# 400_TEENSY.net
KiCad netlist of a schematic drawn in Altium Designer
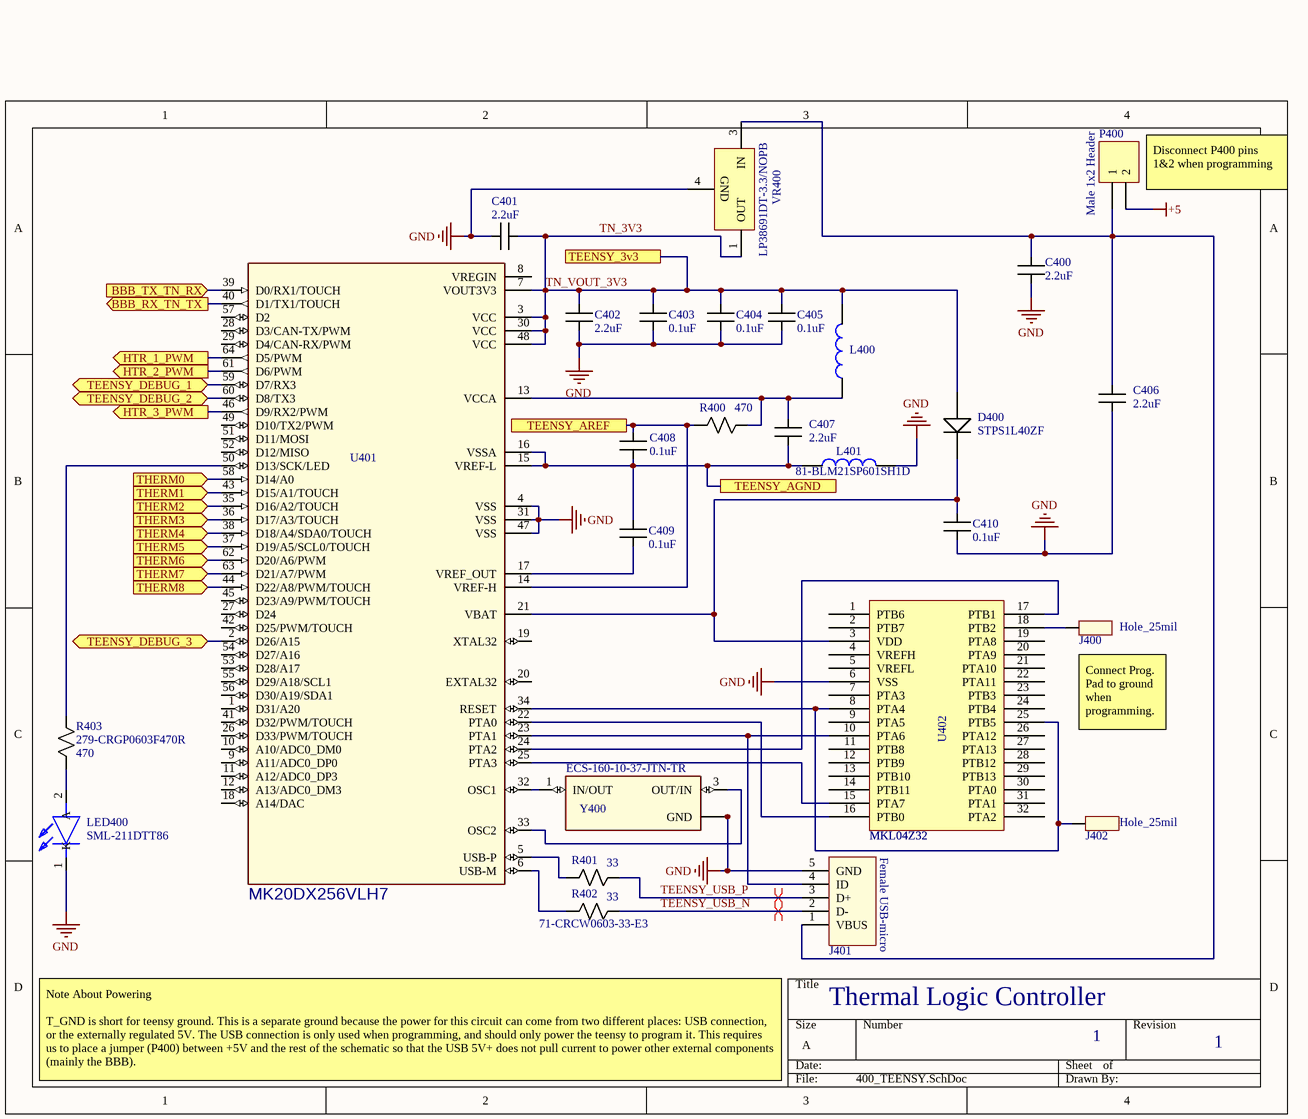
[diagram p0: 400_TEENSY.SchDoc]

(export (version "E")
  (design (tool "Eeschema 10.0.6"))
  (components
    (comp (ref "C400")
      (value "2.2uF")
      (footprint "IMPERIAL0603_Capacitor")
      (description "2.2uF Capacitor, Non Polarized Chip Cap")
      (fields (field (name "Comment") "2.2uF Capacitor"))
      (libsource (lib "OASIS_COMPONENTS_SYMBOLS") (part "LMK107BJ225KK-T"))
    )
    (comp (ref "C401")
      (value "2.2uF")
      (footprint "IMPERIAL0603_Capacitor")
      (description "2.2uF Capacitor, Non Polarized Chip Cap")
      (fields (field (name "Comment") "2.2uF Capacitor"))
      (libsource (lib "OASIS_COMPONENTS_SYMBOLS") (part "LMK107BJ225KK-T"))
    )
    (comp (ref "C402")
      (value "2.2uF")
      (footprint "IMPERIAL0603_Capacitor")
      (description "2.2uF Capacitor, Non Polarized Chip Cap")
      (fields (field (name "Comment") "2.2uF Capacitor"))
      (libsource (lib "OASIS_COMPONENTS_SYMBOLS") (part "LMK107BJ225KK-T"))
    )
    (comp (ref "C403")
      (value "0.1uF")
      (footprint "IMPERIAL0603_Capacitor")
      (description "0.1uF capacitor, Non Polarized Chip Cap")
      (fields (field (name "Comment") "0.1uF Capactor"))
      (libsource (lib "OASIS_COMPONENTS_SYMBOLS") (part "TMK107BJ104KA-T"))
    )
    (comp (ref "C404")
      (value "0.1uF")
      (footprint "IMPERIAL0603_Capacitor")
      (description "0.1uF capacitor, Non Polarized Chip Cap")
      (fields (field (name "Comment") "0.1uF Capactor"))
      (libsource (lib "OASIS_COMPONENTS_SYMBOLS") (part "TMK107BJ104KA-T"))
    )
    (comp (ref "C405")
      (value "0.1uF")
      (footprint "IMPERIAL0603_Capacitor")
      (description "0.1uF capacitor, Non Polarized Chip Cap")
      (fields (field (name "Comment") "0.1uF Capactor"))
      (libsource (lib "OASIS_COMPONENTS_SYMBOLS") (part "TMK107BJ104KA-T"))
    )
    (comp (ref "C406")
      (value "2.2uF")
      (footprint "IMPERIAL0603_Capacitor")
      (description "2.2uF Capacitor, Non Polarized Chip Cap")
      (fields (field (name "Comment") "2.2uF Capacitor"))
      (libsource (lib "OASIS_COMPONENTS_SYMBOLS") (part "LMK107BJ225KK-T"))
    )
    (comp (ref "C407")
      (value "2.2uF")
      (footprint "IMPERIAL0603_Capacitor")
      (description "2.2uF Capacitor, Non Polarized Chip Cap")
      (fields (field (name "Comment") "2.2uF Capacitor"))
      (libsource (lib "OASIS_COMPONENTS_SYMBOLS") (part "LMK107BJ225KK-T"))
    )
    (comp (ref "C408")
      (value "0.1uF")
      (footprint "IMPERIAL0603_Capacitor")
      (description "0.1uF capacitor, Non Polarized Chip Cap")
      (fields (field (name "Comment") "0.1uF Capactor"))
      (libsource (lib "OASIS_COMPONENTS_SYMBOLS") (part "TMK107BJ104KA-T"))
    )
    (comp (ref "C409")
      (value "0.1uF")
      (footprint "IMPERIAL0603_Capacitor")
      (description "0.1uF capacitor, Non Polarized Chip Cap")
      (fields (field (name "Comment") "0.1uF Capactor"))
      (libsource (lib "OASIS_COMPONENTS_SYMBOLS") (part "TMK107BJ104KA-T"))
    )
    (comp (ref "C410")
      (value "0.1uF")
      (footprint "IMPERIAL0603_Capacitor")
      (description "0.1uF capacitor, Non Polarized Chip Cap")
      (fields (field (name "Comment") "0.1uF Capactor"))
      (libsource (lib "OASIS_COMPONENTS_SYMBOLS") (part "TMK107BJ104KA-T"))
    )
    (comp (ref "D400")
      (value "STPS1L40ZF")
      (footprint "*SODFL3718X108N")
      (description "1A Schottky Diode")
      (libsource (lib "OASIS_COMPONENTS_SYMBOLS") (part "STPS1L40ZF"))
    )
    (comp (ref "J400")
      (value "Hole_25mil")
      (footprint "PAD_40x25")
      (description "40 mil solder pad - 25 mil hole")
      (libsource (lib "OASIS_COMPONENTS_SYMBOLS") (part "Hole_25mil"))
    )
    (comp (ref "J401")
      (value "uUSB Padsonly")
      (footprint "uUSB_Padsonly")
      (description "Micro USB Connection - solder pads only")
      (libsource (lib "OASIS_COMPONENTS_SYMBOLS") (part "uUSB_Padsonly"))
    )
    (comp (ref "J402")
      (value "Hole_25mil")
      (footprint "PAD_40x25")
      (description "40 mil solder pad - 25 mil hole")
      (libsource (lib "OASIS_COMPONENTS_SYMBOLS") (part "Hole_25mil"))
    )
    (comp (ref "L400")
      (value "Ferritde, 600 Ohm Impedence")
      (footprint "Imperial0805_RES")
      (description "Ferrite Bead, 600 Ohm Impedence for TLC")
      (fields (field (name "SUPPLIER PART NUMBER 1") "81-BLM21SP601SH1D"))
      (libsource (lib "OASIS_COMPONENTS_SYMBOLS") (part "BLM21SP601SH1D"))
    )
    (comp (ref "L401")
      (value "Ferritde, 600 Ohm Impedence")
      (footprint "Imperial0805_RES")
      (description "Ferrite Bead, 600 Ohm Impedence for TLC")
      (libsource (lib "OASIS_COMPONENTS_SYMBOLS") (part "BLM21SP601SH1D"))
    )
    (comp (ref "LED400")
      (value "SML-211DTT86")
      (footprint "OASIS_COMPONENTS_FOOTPRINTS:LEDC2012X90N")
      (description "LED")
      (libsource (lib "OASIS_COMPONENTS_SYMBOLS") (part "SML-211DTT86"))
    )
    (comp (ref "P400")
      (value "Header 2")
      (footprint "HDR1X2")
      (description "Header, 2-Pin")
      (fields (field (name "PUBLISHER") "Altium Limited"))
      (libsource (lib "Miscellaneous Connectors") (part "Header 2"))
    )
    (comp (ref "R400")
      (value "470")
      (footprint "Imperial0603_RES")
      (description "470 Ohm Generic Chip Resistor")
      (fields (field (name "Comment") "470 Ohm Resistor"))
      (libsource (lib "OASIS_COMPONENTS_SYMBOLS") (part "CRGP0603F470R"))
    )
    (comp (ref "R401")
      (value "33")
      (footprint "Imperial0603_RES")
      (description "33 Ohm Generic Chip Resistor")
      (fields (field (name "Comment") "33 Ohm Resistor"))
      (libsource (lib "OASIS_COMPONENTS_SYMBOLS") (part "CRCW060333R0FKEAC"))
    )
    (comp (ref "R402")
      (value "33")
      (footprint "Imperial0603_RES")
      (description "33 Ohm Generic Chip Resistor")
      (fields
        (field (name "SUPPLIER PART NUMBER 1") "71-CRCW0603-33-E3")
        (field (name "Comment") "33 Ohm Resistor")
      )
      (libsource (lib "OASIS_COMPONENTS_SYMBOLS") (part "CRCW060333R0FKEAC"))
    )
    (comp (ref "R403")
      (value "470")
      (footprint "Imperial0603_RES")
      (description "470 Ohm Generic Chip Resistor")
      (fields
        (field (name "SUPPLIER PART NUMBER 1") "279-CRGP0603F470R")
        (field (name "Comment") "470 Ohm Resistor")
      )
      (libsource (lib "OASIS_COMPONENTS_SYMBOLS") (part "CRGP0603F470R"))
    )
    (comp (ref "U401")
      (value "MK20DX256VLH7")
      (footprint "*QFP50P1200X1200X160-64N")
      (description "MCU 32-bit Kinetis K20 ARM Cortex M4 RISC 256KB Flash 1.8V/2.5V/3.3V 64-Pin LQFP Tray")
      (fields (field (name "MF") "NXP USA") (field (name "MP") "MK20DX256VLH7"))
      (libsource (lib "OASIS_COMPONENTS_SYMBOLS") (part "MK20DX256VLH7"))
    )
    (comp (ref "U402")
      (value "MKL04Z32")
      (footprint "*QFP80P900X900X160-32N")
      (description "Bootloader chip for teensy 3.2")
      (fields (field (name "PART NUMBER") "MKL04Z32"))
      (libsource (lib "OASIS_COMPONENTS_SYMBOLS") (part "MKL04Z32"))
    )
    (comp (ref "VR400")
      (value "LP38691DT-3.3/NOPB")
      (footprint "NDP0003B_N")
      (fields (field (name "MANUFACTURER") "Texas Instruments"))
      (libsource (lib "OASIS_COMPONENTS_SYMBOLS") (part "CMP-0062-00443-4"))
    )
    (comp (ref "Y400")
      (value "ECS-160-10-37-JTN-TR")
      (footprint "XTAL_ECS-160-10-37-RWM-TR")
      (description "Crystal 16MHz")
      (fields (field (name "DIGI-KEY_PART_NUMBER") "XC2119CT-ND") (field (name "MF") "ECS Inc."))
      (libsource (lib "OASIS_COMPONENTS_SYMBOLS") (part "ECS-160-10-37-JTN-TR"))
    )
  )
  (nets
    (net (code "1") (name "+5") (class "Default")
      (node (ref "P400") (pin "2") (pinfunction "2_2") (pintype "passive"))
    )
    (net (code "2") (name "/BBB_RX_TN_TX") (class "Default")
      (node (ref "U401") (pin "40") (pinfunction "D1/TX1/TOUCH_40") (pintype "output"))
    )
    (net (code "3") (name "/BBB_TX_TN_RX") (class "Default")
      (node (ref "U401") (pin "39") (pinfunction "D0/RX1/TOUCH_39") (pintype "input"))
    )
    (net (code "4") (name "/HTR_1_PWM") (class "Default")
      (node (ref "U401") (pin "64") (pinfunction "D5/PWM_64") (pintype "output"))
    )
    (net (code "5") (name "/HTR_2_PWM") (class "Default")
      (node (ref "U401") (pin "61") (pinfunction "D6/PWM_61") (pintype "output"))
    )
    (net (code "6") (name "/HTR_3_PWM") (class "Default")
      (node (ref "U401") (pin "46") (pinfunction "D9/RX2/PWM_46") (pintype "output"))
    )
    (net (code "7") (name "/TEENSY_AGND") (class "Default")
      (node (ref "C407") (pin "2") (pinfunction "2_2") (pintype "passive"))
      (node (ref "C408") (pin "2") (pinfunction "2_2") (pintype "passive"))
      (node (ref "C409") (pin "1") (pinfunction "1_1") (pintype "passive"))
      (node (ref "L401") (pin "1") (pinfunction "1_1") (pintype "passive"))
      (node (ref "U401") (pin "15") (pinfunction "VREF-L_15") (pintype "power_in"))
      (node (ref "U401") (pin "16") (pinfunction "VSSA_16") (pintype "power_in"))
    )
    (net (code "8") (name "/TEENSY_AREF") (class "Default")
      (node (ref "C408") (pin "1") (pinfunction "1_1") (pintype "passive"))
      (node (ref "R400") (pin "1") (pinfunction "1_1") (pintype "passive"))
      (node (ref "U401") (pin "14") (pinfunction "VREF-H_14") (pintype "power_in"))
    )
    (net (code "9") (name "/TEENSY_DEBUG_1") (class "Default")
      (node (ref "U401") (pin "59") (pinfunction "D7/RX3_59") (pintype "bidirectional"))
    )
    (net (code "10") (name "/TEENSY_DEBUG_2") (class "Default")
      (node (ref "U401") (pin "60") (pinfunction "D8/TX3_60") (pintype "bidirectional"))
    )
    (net (code "11") (name "/TEENSY_DEBUG_3") (class "Default")
      (node (ref "U401") (pin "2") (pinfunction "D26/A15_2") (pintype "bidirectional"))
    )
    (net (code "12") (name "/TEENSY_USB_N") (class "Default")
      (node (ref "J401") (pin "2") (pinfunction "D-_2") (pintype "passive"))
      (node (ref "R402") (pin "2") (pinfunction "2_2") (pintype "passive"))
    )
    (net (code "13") (name "/TEENSY_USB_P") (class "Default")
      (node (ref "J401") (pin "3") (pinfunction "D+_3") (pintype "passive"))
      (node (ref "R401") (pin "2") (pinfunction "2_2") (pintype "passive"))
    )
    (net (code "14") (name "/THERM0") (class "Default")
      (node (ref "U401") (pin "58") (pinfunction "D14/A0_58") (pintype "input"))
    )
    (net (code "15") (name "/THERM1") (class "Default")
      (node (ref "U401") (pin "43") (pinfunction "D15/A1/TOUCH_43") (pintype "input"))
    )
    (net (code "16") (name "/THERM2") (class "Default")
      (node (ref "U401") (pin "35") (pinfunction "D16/A2/TOUCH_35") (pintype "input"))
    )
    (net (code "17") (name "/THERM3") (class "Default")
      (node (ref "U401") (pin "36") (pinfunction "D17/A3/TOUCH_36") (pintype "input"))
    )
    (net (code "18") (name "/THERM4") (class "Default")
      (node (ref "U401") (pin "38") (pinfunction "D18/A4/SDA0/TOUCH_38") (pintype "input"))
    )
    (net (code "19") (name "/THERM5") (class "Default")
      (node (ref "U401") (pin "37") (pinfunction "D19/A5/SCL0/TOUCH_37") (pintype "input"))
    )
    (net (code "20") (name "/THERM6") (class "Default")
      (node (ref "U401") (pin "62") (pinfunction "D20/A6/PWM_62") (pintype "input"))
    )
    (net (code "21") (name "/THERM7") (class "Default")
      (node (ref "U401") (pin "63") (pinfunction "D21/A7/PWM_63") (pintype "input"))
    )
    (net (code "22") (name "/THERM8") (class "Default")
      (node (ref "U401") (pin "44") (pinfunction "D22/A8/PWM/TOUCH_44") (pintype "input"))
    )
    (net (code "23") (name "/TN_3V3") (class "Default")
      (node (ref "C401") (pin "1") (pinfunction "1_1") (pintype "passive"))
      (node (ref "C402") (pin "1") (pinfunction "1_1") (pintype "passive"))
      (node (ref "C403") (pin "1") (pinfunction "1_1") (pintype "passive"))
      (node (ref "C404") (pin "1") (pinfunction "1_1") (pintype "passive"))
      (node (ref "C405") (pin "1") (pinfunction "1_1") (pintype "passive"))
      (node (ref "D400") (pin "2") (pinfunction "anode_2") (pintype "passive"))
      (node (ref "L400") (pin "2") (pinfunction "2_2") (pintype "passive"))
      (node (ref "U401") (pin "3") (pinfunction "VCC_3") (pintype "power_in"))
      (node (ref "U401") (pin "30") (pinfunction "VCC_30") (pintype "power_in"))
      (node (ref "U401") (pin "48") (pinfunction "VCC_48") (pintype "power_in"))
      (node (ref "U401") (pin "7") (pinfunction "VOUT3V3_7") (pintype "power_in"))
      (node (ref "VR400") (pin "1") (pinfunction "OUT_1") (pintype "power_in"))
    )
    (net (code "24") (name "GND") (class "Default")
      (node (ref "C400") (pin "2") (pinfunction "2_2") (pintype "passive"))
      (node (ref "C401") (pin "2") (pinfunction "2_2") (pintype "passive"))
      (node (ref "C402") (pin "2") (pinfunction "2_2") (pintype "passive"))
      (node (ref "C403") (pin "2") (pinfunction "2_2") (pintype "passive"))
      (node (ref "C404") (pin "2") (pinfunction "2_2") (pintype "passive"))
      (node (ref "C405") (pin "2") (pinfunction "2_2") (pintype "passive"))
      (node (ref "C406") (pin "2") (pinfunction "2_2") (pintype "passive"))
      (node (ref "C410") (pin "2") (pinfunction "2_2") (pintype "passive"))
      (node (ref "J401") (pin "5") (pinfunction "GND_5") (pintype "passive"))
      (node (ref "L401") (pin "2") (pinfunction "2_2") (pintype "passive"))
      (node (ref "LED400") (pin "1") (pinfunction "K_1") (pintype "passive"))
      (node (ref "U401") (pin "31") (pinfunction "VSS_31") (pintype "power_in"))
      (node (ref "U401") (pin "4") (pinfunction "VSS_4") (pintype "power_in"))
      (node (ref "U401") (pin "47") (pinfunction "VSS_47") (pintype "power_in"))
      (node (ref "U402") (pin "6") (pinfunction "VSS_6") (pintype "passive"))
      (node (ref "VR400") (pin "4") (pinfunction "GND_4") (pintype "power_in"))
      (node (ref "Y400") (pin "2") (pinfunction "GND_2") (pintype "power_in"))
      (node (ref "Y400") (pin "4") (pinfunction "GND_4") (pintype "power_in"))
    )
    (net (code "25") (name "Net-(D400-cathode)") (class "Default")
      (node (ref "C410") (pin "1") (pinfunction "1_1") (pintype "passive"))
      (node (ref "D400") (pin "1") (pinfunction "cathode_1") (pintype "passive"))
      (node (ref "U401") (pin "21") (pinfunction "VBAT_21") (pintype "power_in"))
      (node (ref "U402") (pin "3") (pinfunction "VDD_3") (pintype "passive"))
    )
    (net (code "26") (name "Net-(J400-PIN)") (class "Default")
      (node (ref "J400") (pin "1") (pinfunction "PIN_1") (pintype "passive"))
      (node (ref "U402") (pin "18") (pinfunction "PTB2_18") (pintype "passive"))
    )
    (net (code "27") (name "Net-(J401-ID)") (class "Default")
      (node (ref "J401") (pin "4") (pinfunction "ID_4") (pintype "passive"))
      (node (ref "U401") (pin "23") (pinfunction "PTA1_23") (pintype "bidirectional"))
      (node (ref "U402") (pin "10") (pinfunction "PTA6_10") (pintype "passive"))
    )
    (net (code "28") (name "Net-(J401-VBUS)") (class "Default")
      (node (ref "C400") (pin "1") (pinfunction "1_1") (pintype "passive"))
      (node (ref "C406") (pin "1") (pinfunction "1_1") (pintype "passive"))
      (node (ref "J401") (pin "1") (pinfunction "VBUS_1") (pintype "passive"))
      (node (ref "P400") (pin "1") (pinfunction "1_1") (pintype "passive"))
      (node (ref "VR400") (pin "3") (pinfunction "IN_3") (pintype "power_in"))
    )
    (net (code "29") (name "Net-(J402-PIN)") (class "Default")
      (node (ref "J402") (pin "1") (pinfunction "PIN_1") (pintype "passive"))
      (node (ref "U401") (pin "34") (pinfunction "RESET_34") (pintype "bidirectional"))
      (node (ref "U402") (pin "25") (pinfunction "PTB5_25") (pintype "passive"))
      (node (ref "U402") (pin "8") (pinfunction "PTA4_8") (pintype "passive"))
    )
    (net (code "30") (name "Net-(LED400-A)") (class "Default")
      (node (ref "LED400") (pin "2") (pinfunction "A_2") (pintype "passive"))
      (node (ref "R403") (pin "1") (pinfunction "1_1") (pintype "passive"))
    )
    (net (code "31") (name "Net-(U401-D13{slash}SCK{slash}LED)") (class "Default")
      (node (ref "R403") (pin "2") (pinfunction "2_2") (pintype "passive"))
      (node (ref "U401") (pin "50") (pinfunction "D13/SCK/LED_50") (pintype "bidirectional"))
    )
    (net (code "32") (name "Net-(U401-OSC1)") (class "Default")
      (node (ref "U401") (pin "32") (pinfunction "OSC1_32") (pintype "bidirectional"))
      (node (ref "Y400") (pin "1") (pinfunction "IN/OUT_1") (pintype "bidirectional"))
    )
    (net (code "33") (name "Net-(U401-OSC2)") (class "Default")
      (node (ref "U401") (pin "33") (pinfunction "OSC2_33") (pintype "bidirectional"))
      (node (ref "Y400") (pin "3") (pinfunction "OUT/IN_3") (pintype "bidirectional"))
    )
    (net (code "34") (name "Net-(U401-PTA0)") (class "Default")
      (node (ref "U401") (pin "22") (pinfunction "PTA0_22") (pintype "bidirectional"))
      (node (ref "U402") (pin "16") (pinfunction "PTB0_16") (pintype "passive"))
    )
    (net (code "35") (name "Net-(U401-PTA2)") (class "Default")
      (node (ref "U401") (pin "24") (pinfunction "PTA2_24") (pintype "bidirectional"))
      (node (ref "U402") (pin "17") (pinfunction "PTB1_17") (pintype "passive"))
    )
    (net (code "36") (name "Net-(U401-PTA3)") (class "Default")
      (node (ref "U401") (pin "25") (pinfunction "PTA3_25") (pintype "bidirectional"))
      (node (ref "U402") (pin "15") (pinfunction "PTA7_15") (pintype "passive"))
    )
    (net (code "37") (name "Net-(U401-USB-M)") (class "Default")
      (node (ref "R402") (pin "1") (pinfunction "1_1") (pintype "passive"))
      (node (ref "U401") (pin "6") (pinfunction "USB-M_6") (pintype "bidirectional"))
    )
    (net (code "38") (name "Net-(U401-USB-P)") (class "Default")
      (node (ref "R401") (pin "1") (pinfunction "1_1") (pintype "passive"))
      (node (ref "U401") (pin "5") (pinfunction "USB-P_5") (pintype "bidirectional"))
    )
    (net (code "39") (name "Net-(U401-VCCA)") (class "Default")
      (node (ref "C407") (pin "1") (pinfunction "1_1") (pintype "passive"))
      (node (ref "L400") (pin "1") (pinfunction "1_1") (pintype "passive"))
      (node (ref "R400") (pin "2") (pinfunction "2_2") (pintype "passive"))
      (node (ref "U401") (pin "13") (pinfunction "VCCA_13") (pintype "power_in"))
    )
    (net (code "40") (name "Net-(U401-VREF_OUT)") (class "Default")
      (node (ref "C409") (pin "2") (pinfunction "2_2") (pintype "passive"))
      (node (ref "U401") (pin "17") (pinfunction "VREF_OUT_17") (pintype "power_in"))
    )
    (net (code "41") (name "unconnected-(U401-A10{slash}ADC0_DM0-Pad10)") (class "Default")
      (node (ref "U401") (pin "10") (pinfunction "A10/ADC0_DM0_10") (pintype "bidirectional"))
    )
    (net (code "42") (name "unconnected-(U401-A11{slash}ADC0_DP0-Pad9)") (class "Default")
      (node (ref "U401") (pin "9") (pinfunction "A11/ADC0_DP0_9") (pintype "bidirectional"))
    )
    (net (code "43") (name "unconnected-(U401-A12{slash}ADC0_DP3-Pad11)") (class "Default")
      (node (ref "U401") (pin "11") (pinfunction "A12/ADC0_DP3_11") (pintype "bidirectional"))
    )
    (net (code "44") (name "unconnected-(U401-A13{slash}ADC0_DM3-Pad12)") (class "Default")
      (node (ref "U401") (pin "12") (pinfunction "A13/ADC0_DM3_12") (pintype "bidirectional"))
    )
    (net (code "45") (name "unconnected-(U401-A14{slash}DAC-Pad18)") (class "Default")
      (node (ref "U401") (pin "18") (pinfunction "A14/DAC_18") (pintype "bidirectional"))
    )
    (net (code "46") (name "unconnected-(U401-D2-Pad57)") (class "Default")
      (node (ref "U401") (pin "57") (pinfunction "D2_57") (pintype "bidirectional"))
    )
    (net (code "47") (name "unconnected-(U401-D3{slash}CAN-TX{slash}PWM-Pad28)") (class "Default")
      (node (ref "U401") (pin "28") (pinfunction "D3/CAN-TX/PWM_28") (pintype "bidirectional"))
    )
    (net (code "48") (name "unconnected-(U401-D4{slash}CAN-RX{slash}PWM-Pad29)") (class "Default")
      (node (ref "U401") (pin "29") (pinfunction "D4/CAN-RX/PWM_29") (pintype "bidirectional"))
    )
    (net (code "49") (name "unconnected-(U401-D10{slash}TX2{slash}PWM-Pad49)") (class "Default")
      (node (ref "U401") (pin "49") (pinfunction "D10/TX2/PWM_49") (pintype "bidirectional"))
    )
    (net (code "50") (name "unconnected-(U401-D11{slash}MOSI-Pad51)") (class "Default")
      (node (ref "U401") (pin "51") (pinfunction "D11/MOSI_51") (pintype "bidirectional"))
    )
    (net (code "51") (name "unconnected-(U401-D12{slash}MISO-Pad52)") (class "Default")
      (node (ref "U401") (pin "52") (pinfunction "D12/MISO_52") (pintype "bidirectional"))
    )
    (net (code "52") (name "unconnected-(U401-D23{slash}A9{slash}PWM{slash}TOUCH-Pad45)") (class "Default")
      (node (ref "U401") (pin "45") (pinfunction "D23/A9/PWM/TOUCH_45") (pintype "bidirectional"))
    )
    (net (code "53") (name "unconnected-(U401-D24-Pad27)") (class "Default")
      (node (ref "U401") (pin "27") (pinfunction "D24_27") (pintype "bidirectional"))
    )
    (net (code "54") (name "unconnected-(U401-D25{slash}PWM{slash}TOUCH-Pad42)") (class "Default")
      (node (ref "U401") (pin "42") (pinfunction "D25/PWM/TOUCH_42") (pintype "bidirectional"))
    )
    (net (code "55") (name "unconnected-(U401-D27{slash}A16-Pad54)") (class "Default")
      (node (ref "U401") (pin "54") (pinfunction "D27/A16_54") (pintype "bidirectional"))
    )
    (net (code "56") (name "unconnected-(U401-D28{slash}A17-Pad53)") (class "Default")
      (node (ref "U401") (pin "53") (pinfunction "D28/A17_53") (pintype "bidirectional"))
    )
    (net (code "57") (name "unconnected-(U401-D29{slash}A18{slash}SCL1-Pad55)") (class "Default")
      (node (ref "U401") (pin "55") (pinfunction "D29/A18/SCL1_55") (pintype "bidirectional"))
    )
    (net (code "58") (name "unconnected-(U401-D30{slash}A19{slash}SDA1-Pad56)") (class "Default")
      (node (ref "U401") (pin "56") (pinfunction "D30/A19/SDA1_56") (pintype "bidirectional"))
    )
    (net (code "59") (name "unconnected-(U401-D31{slash}A20-Pad1)") (class "Default")
      (node (ref "U401") (pin "1") (pinfunction "D31/A20_1") (pintype "bidirectional"))
    )
    (net (code "60") (name "unconnected-(U401-D32{slash}PWM{slash}TOUCH-Pad41)") (class "Default")
      (node (ref "U401") (pin "41") (pinfunction "D32/PWM/TOUCH_41") (pintype "bidirectional"))
    )
    (net (code "61") (name "unconnected-(U401-D33{slash}PWM{slash}TOUCH-Pad26)") (class "Default")
      (node (ref "U401") (pin "26") (pinfunction "D33/PWM/TOUCH_26") (pintype "bidirectional"))
    )
    (net (code "62") (name "unconnected-(U401-EXTAL32-Pad20)") (class "Default")
      (node (ref "U401") (pin "20") (pinfunction "EXTAL32_20") (pintype "bidirectional"))
    )
    (net (code "63") (name "unconnected-(U401-VREGIN-Pad8)") (class "Default")
      (node (ref "U401") (pin "8") (pinfunction "VREGIN_8") (pintype "power_in"))
    )
    (net (code "64") (name "unconnected-(U401-XTAL32-Pad19)") (class "Default")
      (node (ref "U401") (pin "19") (pinfunction "XTAL32_19") (pintype "bidirectional"))
    )
    (net (code "65") (name "unconnected-(U402-PTA0-Pad30)") (class "Default")
      (node (ref "U402") (pin "30") (pinfunction "PTA0_30") (pintype "passive"))
    )
    (net (code "66") (name "unconnected-(U402-PTA1-Pad31)") (class "Default")
      (node (ref "U402") (pin "31") (pinfunction "PTA1_31") (pintype "passive"))
    )
    (net (code "67") (name "unconnected-(U402-PTA2-Pad32)") (class "Default")
      (node (ref "U402") (pin "32") (pinfunction "PTA2_32") (pintype "passive"))
    )
    (net (code "68") (name "unconnected-(U402-PTA3-Pad7)") (class "Default")
      (node (ref "U402") (pin "7") (pinfunction "PTA3_7") (pintype "passive"))
    )
    (net (code "69") (name "unconnected-(U402-PTA5-Pad9)") (class "Default")
      (node (ref "U402") (pin "9") (pinfunction "PTA5_9") (pintype "passive"))
    )
    (net (code "70") (name "unconnected-(U402-PTA8-Pad19)") (class "Default")
      (node (ref "U402") (pin "19") (pinfunction "PTA8_19") (pintype "passive"))
    )
    (net (code "71") (name "unconnected-(U402-PTA9-Pad20)") (class "Default")
      (node (ref "U402") (pin "20") (pinfunction "PTA9_20") (pintype "passive"))
    )
    (net (code "72") (name "unconnected-(U402-PTA10-Pad21)") (class "Default")
      (node (ref "U402") (pin "21") (pinfunction "PTA10_21") (pintype "passive"))
    )
    (net (code "73") (name "unconnected-(U402-PTA11-Pad22)") (class "Default")
      (node (ref "U402") (pin "22") (pinfunction "PTA11_22") (pintype "passive"))
    )
    (net (code "74") (name "unconnected-(U402-PTA12-Pad26)") (class "Default")
      (node (ref "U402") (pin "26") (pinfunction "PTA12_26") (pintype "passive"))
    )
    (net (code "75") (name "unconnected-(U402-PTA13-Pad27)") (class "Default")
      (node (ref "U402") (pin "27") (pinfunction "PTA13_27") (pintype "passive"))
    )
    (net (code "76") (name "unconnected-(U402-PTB3-Pad23)") (class "Default")
      (node (ref "U402") (pin "23") (pinfunction "PTB3_23") (pintype "passive"))
    )
    (net (code "77") (name "unconnected-(U402-PTB4-Pad24)") (class "Default")
      (node (ref "U402") (pin "24") (pinfunction "PTB4_24") (pintype "passive"))
    )
    (net (code "78") (name "unconnected-(U402-PTB6-Pad1)") (class "Default")
      (node (ref "U402") (pin "1") (pinfunction "PTB6_1") (pintype "passive"))
    )
    (net (code "79") (name "unconnected-(U402-PTB7-Pad2)") (class "Default")
      (node (ref "U402") (pin "2") (pinfunction "PTB7_2") (pintype "passive"))
    )
    (net (code "80") (name "unconnected-(U402-PTB8-Pad11)") (class "Default")
      (node (ref "U402") (pin "11") (pinfunction "PTB8_11") (pintype "passive"))
    )
    (net (code "81") (name "unconnected-(U402-PTB9-Pad12)") (class "Default")
      (node (ref "U402") (pin "12") (pinfunction "PTB9_12") (pintype "passive"))
    )
    (net (code "82") (name "unconnected-(U402-PTB10-Pad13)") (class "Default")
      (node (ref "U402") (pin "13") (pinfunction "PTB10_13") (pintype "passive"))
    )
    (net (code "83") (name "unconnected-(U402-PTB11-Pad14)") (class "Default")
      (node (ref "U402") (pin "14") (pinfunction "PTB11_14") (pintype "passive"))
    )
    (net (code "84") (name "unconnected-(U402-PTB12-Pad28)") (class "Default")
      (node (ref "U402") (pin "28") (pinfunction "PTB12_28") (pintype "passive"))
    )
    (net (code "85") (name "unconnected-(U402-PTB13-Pad29)") (class "Default")
      (node (ref "U402") (pin "29") (pinfunction "PTB13_29") (pintype "passive"))
    )
    (net (code "86") (name "unconnected-(U402-VREFH-Pad4)") (class "Default")
      (node (ref "U402") (pin "4") (pinfunction "VREFH_4") (pintype "passive"))
    )
    (net (code "87") (name "unconnected-(U402-VREFL-Pad5)") (class "Default")
      (node (ref "U402") (pin "5") (pinfunction "VREFL_5") (pintype "passive"))
    )
  )
)
